# MicAmplifier.net
KiCad netlist of a schematic drawn in EAGLE
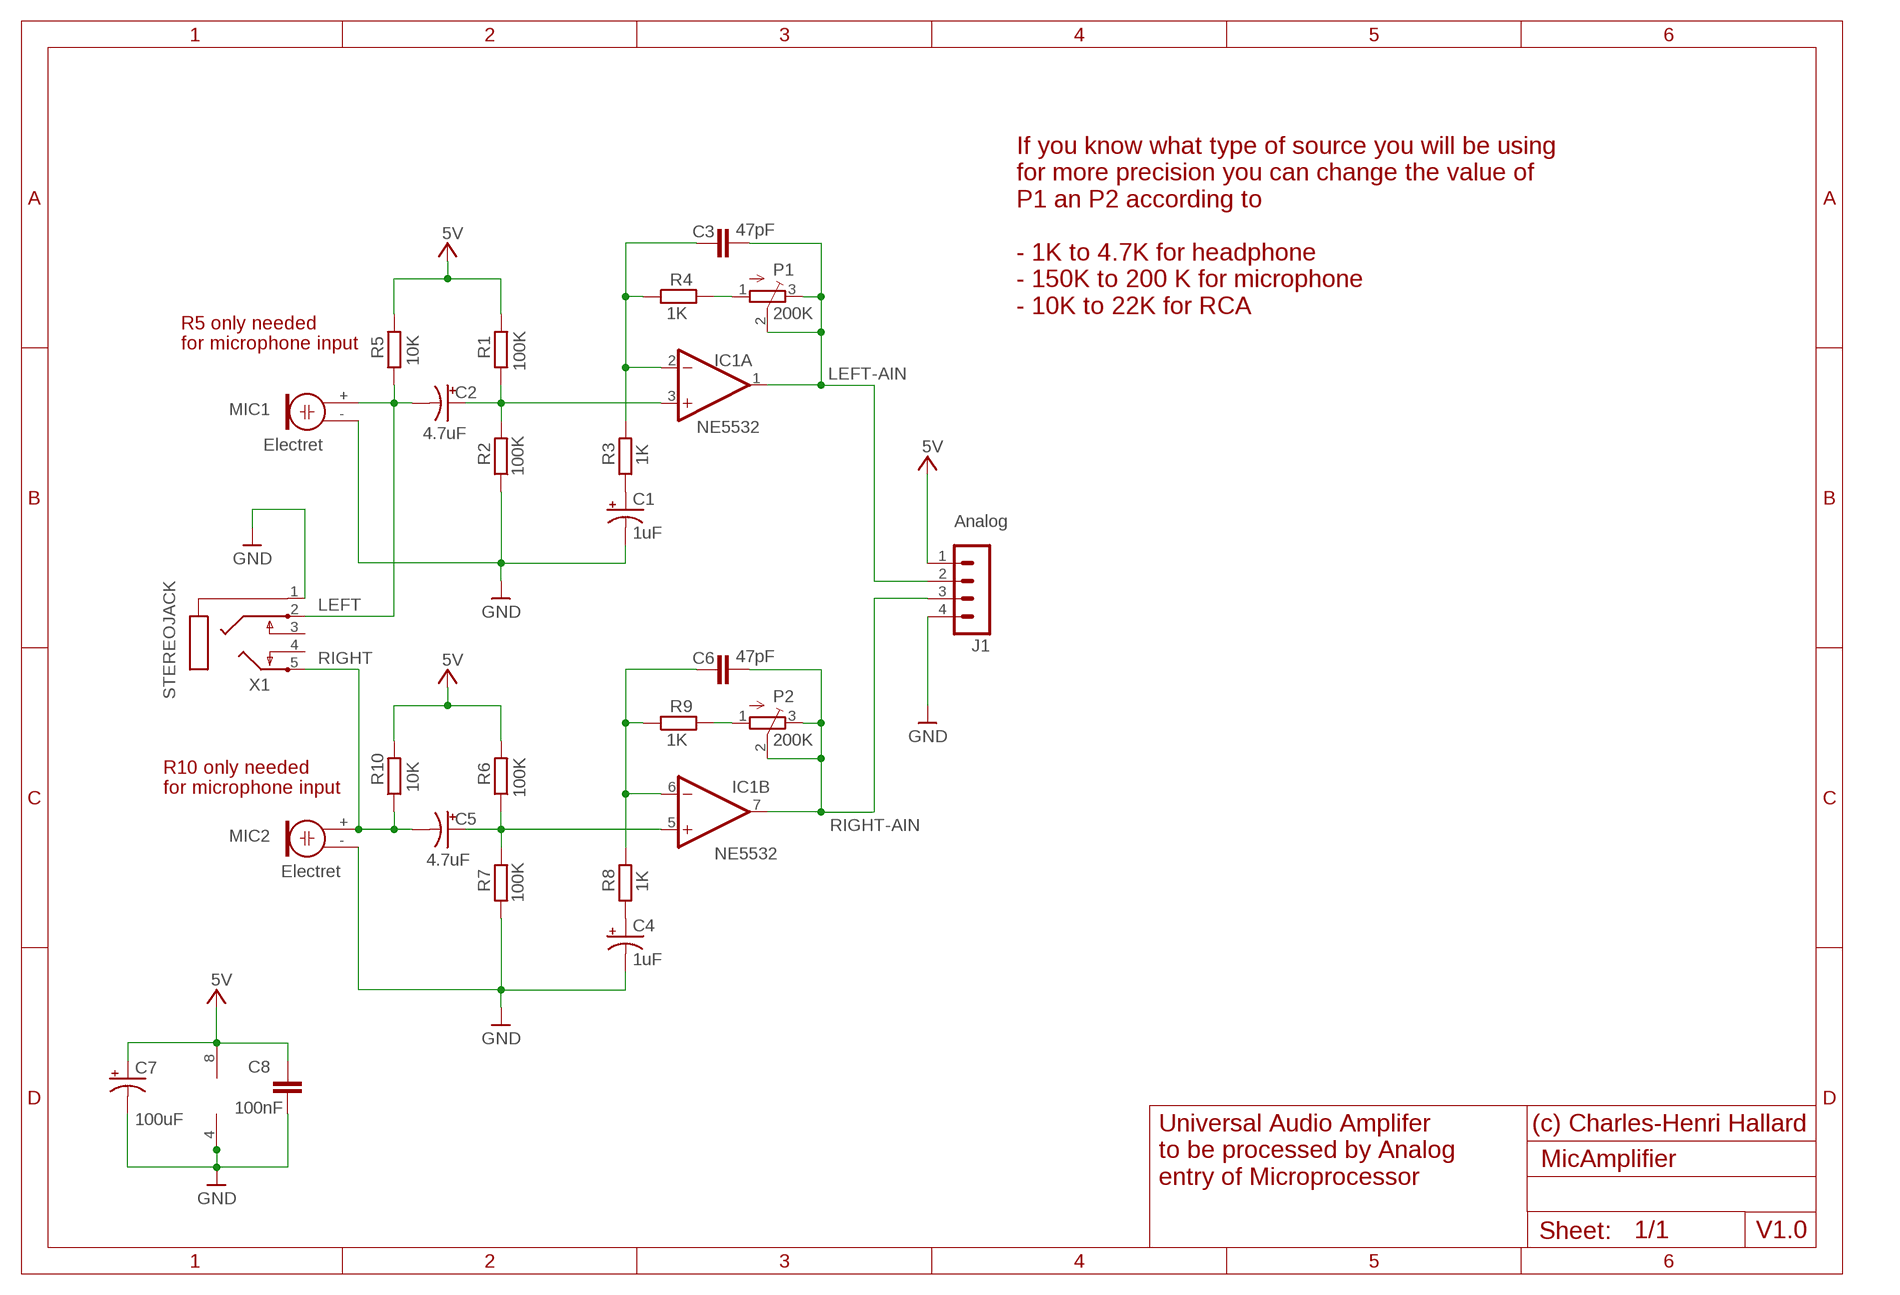
[diagram p0: schematic, sheet 1]

(export (version "E")
  (design (tool "Eeschema 10.0.6"))
  (components
    (comp (ref "C1")
      (value "1uF")
      (footprint "eagle-import:EIA3216")
      (libsource (lib "eagle-import") (part "CAP_POL1206"))
    )
    (comp (ref "C2")
      (value "4.7uF")
      (footprint "eagle-import:EIA3216")
      (libsource (lib "eagle-import") (part "CAP_POL1206"))
    )
    (comp (ref "C3")
      (value "47pF")
      (footprint "eagle-import:C805")
      (libsource (lib "eagle-import") (part "CAPACITOR_NPOL-0805"))
    )
    (comp (ref "C4")
      (value "1uF")
      (footprint "eagle-import:EIA3216")
      (libsource (lib "eagle-import") (part "CAP_POL1206"))
    )
    (comp (ref "C5")
      (value "4.7uF")
      (footprint "eagle-import:EIA3216")
      (libsource (lib "eagle-import") (part "CAP_POL1206"))
    )
    (comp (ref "C6")
      (value "47pF")
      (footprint "eagle-import:C805")
      (libsource (lib "eagle-import") (part "CAPACITOR_NPOL-0805"))
    )
    (comp (ref "C7")
      (value "100uF")
      (footprint "eagle-import:CPOL-RADIAL-10UF-25V")
      (libsource (lib "eagle-import") (part "CAP_POLPTH2"))
    )
    (comp (ref "C8")
      (value "100nF")
      (footprint "eagle-import:C805")
      (libsource (lib "eagle-import") (part "CAPACITOR_NPOL-0805"))
    )
    (comp (ref "IC1")
      (value "NE5532")
      (footprint "eagle-import:SO08")
      (libsource (lib "eagle-import") (part "NE5532D"))
    )
    (comp (ref "J1")
      (value "Analog")
      (footprint "eagle-import:1X04_LOCK")
      (libsource (lib "eagle-import") (part "M04_LOCK"))
    )
    (comp (ref "MIC1")
      (value "Electret")
      (footprint "eagle-import:9.7ELECTRET")
      (libsource (lib "eagle-import") (part "ELECTRET"))
    )
    (comp (ref "MIC2")
      (value "Electret")
      (footprint "eagle-import:9.7ELECTRET")
      (libsource (lib "eagle-import") (part "ELECTRET"))
    )
    (comp (ref "P1")
      (value "200K")
      (footprint "eagle-import:TC33X")
      (libsource (lib "eagle-import") (part "TRIMPOTTC33X"))
    )
    (comp (ref "P2")
      (value "200K")
      (footprint "eagle-import:TC33X")
      (libsource (lib "eagle-import") (part "TRIMPOTTC33X"))
    )
    (comp (ref "R1")
      (value "100K")
      (footprint "eagle-import:R805")
      (libsource (lib "eagle-import") (part "RESISTOR-0805R805"))
    )
    (comp (ref "R2")
      (value "100K")
      (footprint "eagle-import:R805")
      (libsource (lib "eagle-import") (part "RESISTOR-0805R805"))
    )
    (comp (ref "R3")
      (value "1K")
      (footprint "eagle-import:R805")
      (libsource (lib "eagle-import") (part "RESISTOR-0805R805"))
    )
    (comp (ref "R4")
      (value "1K")
      (footprint "eagle-import:R805")
      (libsource (lib "eagle-import") (part "RESISTOR-0805R805"))
    )
    (comp (ref "R5")
      (value "10K")
      (footprint "eagle-import:R805")
      (libsource (lib "eagle-import") (part "RESISTOR-0805R805"))
    )
    (comp (ref "R6")
      (value "100K")
      (footprint "eagle-import:R805")
      (libsource (lib "eagle-import") (part "RESISTOR-0805R805"))
    )
    (comp (ref "R7")
      (value "100K")
      (footprint "eagle-import:R805")
      (libsource (lib "eagle-import") (part "RESISTOR-0805R805"))
    )
    (comp (ref "R8")
      (value "1K")
      (footprint "eagle-import:R805")
      (libsource (lib "eagle-import") (part "RESISTOR-0805R805"))
    )
    (comp (ref "R9")
      (value "1K")
      (footprint "eagle-import:R805")
      (libsource (lib "eagle-import") (part "RESISTOR-0805R805"))
    )
    (comp (ref "R10")
      (value "10K")
      (footprint "eagle-import:R805")
      (libsource (lib "eagle-import") (part "RESISTOR-0805R805"))
    )
    (comp (ref "X1")
      (value "STEREOJACK")
      (footprint "eagle-import:STX3100")
      (libsource (lib "eagle-import") (part "STEREOJACK"))
    )
  )
  (nets
    (net (code "1") (name "/LEFT") (class "Default")
      (node (ref "C2") (pin "C") (pinfunction "-_C") (pintype "passive"))
      (node (ref "MIC1") (pin "+") (pinfunction "2_+") (pintype "passive"))
      (node (ref "R5") (pin "1") (pinfunction "1_1") (pintype "passive"))
      (node (ref "X1") (pin "2") (pinfunction "2_2") (pintype "passive"))
    )
    (net (code "2") (name "/LEFT-AIN") (class "Default")
      (node (ref "C3") (pin "2") (pinfunction "2_2") (pintype "passive"))
      (node (ref "IC1") (pin "1") (pinfunction "OUT_1") (pintype "output"))
      (node (ref "J1") (pin "2") (pinfunction "2_2") (pintype "passive"))
      (node (ref "P1") (pin "2") (pinfunction "S_2") (pintype "passive"))
      (node (ref "P1") (pin "3") (pinfunction "E_3") (pintype "passive"))
    )
    (net (code "3") (name "/RIGHT") (class "Default")
      (node (ref "C5") (pin "C") (pinfunction "-_C") (pintype "passive"))
      (node (ref "MIC2") (pin "+") (pinfunction "2_+") (pintype "passive"))
      (node (ref "R10") (pin "1") (pinfunction "1_1") (pintype "passive"))
      (node (ref "X1") (pin "5") (pinfunction "5_5") (pintype "passive"))
    )
    (net (code "4") (name "/RIGHT-AIN") (class "Default")
      (node (ref "C6") (pin "2") (pinfunction "2_2") (pintype "passive"))
      (node (ref "IC1") (pin "7") (pinfunction "OUT_7") (pintype "output"))
      (node (ref "J1") (pin "3") (pinfunction "3_3") (pintype "passive"))
      (node (ref "P2") (pin "2") (pinfunction "S_2") (pintype "passive"))
      (node (ref "P2") (pin "3") (pinfunction "E_3") (pintype "passive"))
    )
    (net (code "5") (name "5V") (class "Default")
      (node (ref "C7") (pin "1") (pinfunction "+_1") (pintype "passive"))
      (node (ref "C8") (pin "2") (pinfunction "2_2") (pintype "passive"))
      (node (ref "IC1") (pin "8") (pinfunction "V+_8") (pintype "power_in"))
      (node (ref "J1") (pin "1") (pinfunction "1_1") (pintype "passive"))
      (node (ref "R1") (pin "2") (pinfunction "2_2") (pintype "passive"))
      (node (ref "R10") (pin "2") (pinfunction "2_2") (pintype "passive"))
      (node (ref "R5") (pin "2") (pinfunction "2_2") (pintype "passive"))
      (node (ref "R6") (pin "2") (pinfunction "2_2") (pintype "passive"))
    )
    (net (code "6") (name "GND") (class "Default")
      (node (ref "C1") (pin "C") (pinfunction "-_C") (pintype "passive"))
      (node (ref "C4") (pin "C") (pinfunction "-_C") (pintype "passive"))
      (node (ref "C7") (pin "2") (pinfunction "-_2") (pintype "passive"))
      (node (ref "C8") (pin "1") (pinfunction "1_1") (pintype "passive"))
      (node (ref "IC1") (pin "4") (pinfunction "V-_4") (pintype "power_in"))
      (node (ref "J1") (pin "4") (pinfunction "4_4") (pintype "passive"))
      (node (ref "MIC1") (pin "-") (pinfunction "1_-") (pintype "passive"))
      (node (ref "MIC2") (pin "-") (pinfunction "1_-") (pintype "passive"))
      (node (ref "R2") (pin "1") (pinfunction "1_1") (pintype "passive"))
      (node (ref "R7") (pin "1") (pinfunction "1_1") (pintype "passive"))
      (node (ref "X1") (pin "1") (pinfunction "1_1") (pintype "passive"))
    )
    (net (code "7") (name "Net-(C1-+)") (class "Default")
      (node (ref "C1") (pin "A") (pinfunction "+_A") (pintype "passive"))
      (node (ref "R3") (pin "1") (pinfunction "1_1") (pintype "passive"))
    )
    (net (code "8") (name "Net-(C2-+)") (class "Default")
      (node (ref "C2") (pin "A") (pinfunction "+_A") (pintype "passive"))
      (node (ref "IC1") (pin "3") (pinfunction "+IN_3") (pintype "input"))
      (node (ref "R1") (pin "1") (pinfunction "1_1") (pintype "passive"))
      (node (ref "R2") (pin "2") (pinfunction "2_2") (pintype "passive"))
    )
    (net (code "9") (name "Net-(C4-+)") (class "Default")
      (node (ref "C4") (pin "A") (pinfunction "+_A") (pintype "passive"))
      (node (ref "R8") (pin "1") (pinfunction "1_1") (pintype "passive"))
    )
    (net (code "10") (name "Net-(C5-+)") (class "Default")
      (node (ref "C5") (pin "A") (pinfunction "+_A") (pintype "passive"))
      (node (ref "IC1") (pin "5") (pinfunction "+IN_5") (pintype "input"))
      (node (ref "R6") (pin "1") (pinfunction "1_1") (pintype "passive"))
      (node (ref "R7") (pin "2") (pinfunction "2_2") (pintype "passive"))
    )
    (net (code "11") (name "Net-(IC1A--IN)") (class "Default")
      (node (ref "C3") (pin "1") (pinfunction "1_1") (pintype "passive"))
      (node (ref "IC1") (pin "2") (pinfunction "-IN_2") (pintype "input"))
      (node (ref "R3") (pin "2") (pinfunction "2_2") (pintype "passive"))
      (node (ref "R4") (pin "1") (pinfunction "1_1") (pintype "passive"))
    )
    (net (code "12") (name "Net-(IC1B--IN)") (class "Default")
      (node (ref "C6") (pin "1") (pinfunction "1_1") (pintype "passive"))
      (node (ref "IC1") (pin "6") (pinfunction "-IN_6") (pintype "input"))
      (node (ref "R8") (pin "2") (pinfunction "2_2") (pintype "passive"))
      (node (ref "R9") (pin "1") (pinfunction "1_1") (pintype "passive"))
    )
    (net (code "13") (name "Net-(P1-A)") (class "Default")
      (node (ref "P1") (pin "1") (pinfunction "A_1") (pintype "passive"))
      (node (ref "R4") (pin "2") (pinfunction "2_2") (pintype "passive"))
    )
    (net (code "14") (name "Net-(P2-A)") (class "Default")
      (node (ref "P2") (pin "1") (pinfunction "A_1") (pintype "passive"))
      (node (ref "R9") (pin "2") (pinfunction "2_2") (pintype "passive"))
    )
    (net (code "15") (name "unconnected-(X1-Pad3)") (class "Default")
      (node (ref "X1") (pin "3") (pinfunction "3_3") (pintype "passive"))
    )
    (net (code "16") (name "unconnected-(X1-Pad4)") (class "Default")
      (node (ref "X1") (pin "4") (pinfunction "4_4") (pintype "passive"))
    )
  )
)
